# schematic.net
KiCad netlist of a schematic drawn in EAGLE
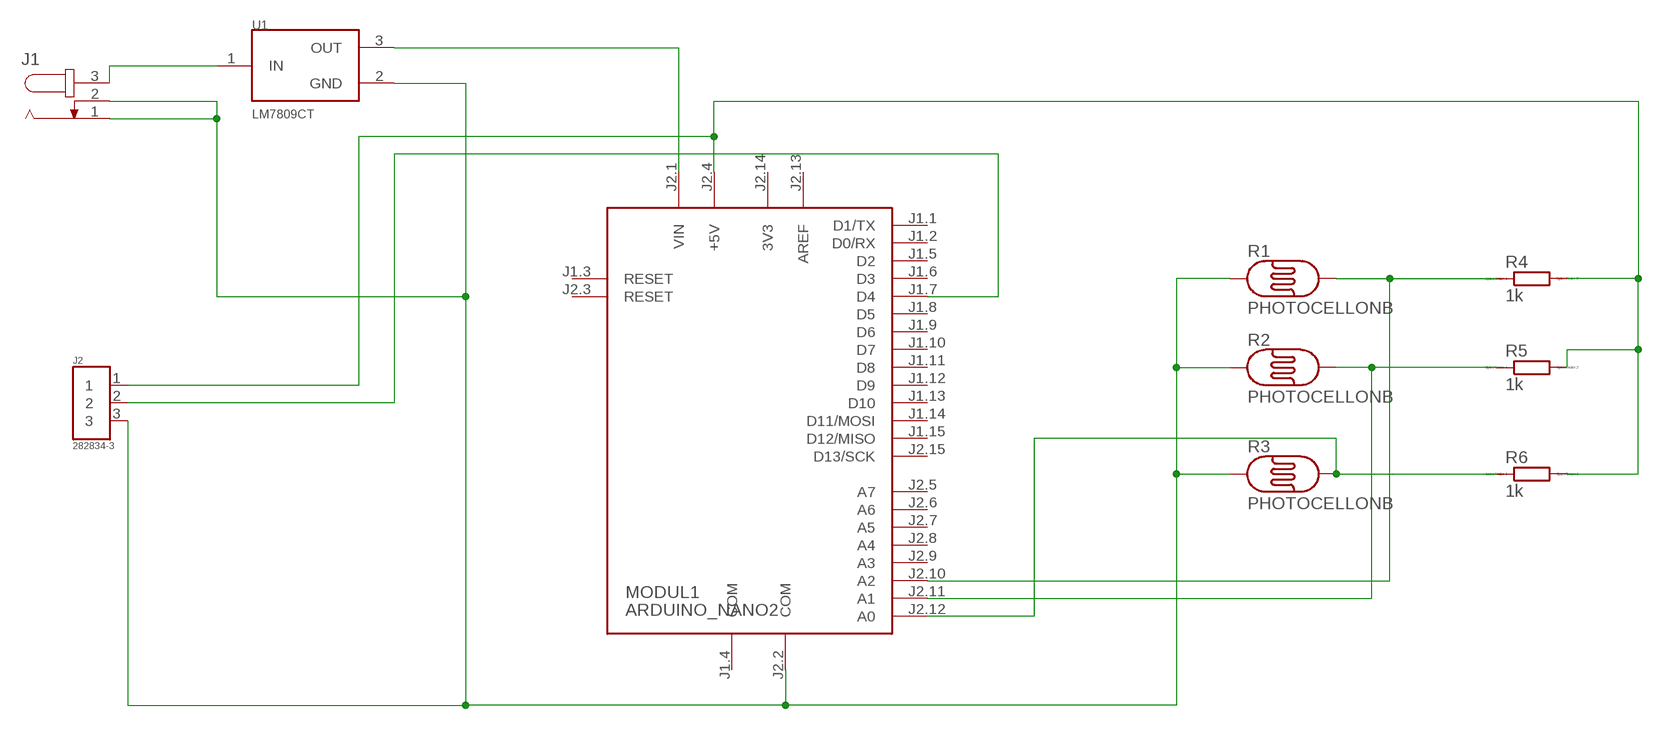
[diagram p0: schematic, sheet 1]

(export (version "E")
  (design (tool "Eeschema 10.0.6"))
  (components
    (comp (ref "J1")
      (value "JACK-PLUG1")
      (footprint "eagle-import:SPC4078")
      (libsource (lib "eagle-import") (part "JACK-PLUG1"))
    )
    (comp (ref "J2")
      (value "282834-3")
      (footprint "eagle-import:TE_282834-3")
      (fields (field (name "MF") "TE Connectivity"))
      (libsource (lib "eagle-import") (part "282834-3"))
    )
    (comp (ref "MODUL1")
      (value "ARDUINO_NANO2")
      (footprint "eagle-import:ARDUINO_NANO2")
      (libsource (lib "eagle-import") (part "ARDUINO_NANO2"))
    )
    (comp (ref "R1")
      (value "PHOTOCELLONB")
      (footprint "eagle-import:ON_BOARD")
      (libsource (lib "eagle-import") (part "PHOTOCELLONB"))
    )
    (comp (ref "R2")
      (value "PHOTOCELLONB")
      (footprint "eagle-import:ON_BOARD")
      (libsource (lib "eagle-import") (part "PHOTOCELLONB"))
    )
    (comp (ref "R3")
      (value "PHOTOCELLONB")
      (footprint "eagle-import:ON_BOARD")
      (libsource (lib "eagle-import") (part "PHOTOCELLONB"))
    )
    (comp (ref "R4")
      (value "1k")
      (footprint "eagle-import:0207_10")
      (libsource (lib "eagle-import") (part "R0207/10"))
    )
    (comp (ref "R5")
      (value "1k")
      (footprint "eagle-import:0207_10")
      (libsource (lib "eagle-import") (part "R0207/10"))
    )
    (comp (ref "R6")
      (value "1k")
      (footprint "eagle-import:0207_10")
      (libsource (lib "eagle-import") (part "R0207/10"))
    )
    (comp (ref "U1")
      (value "LM7809CT")
      (footprint "eagle-import:TO254P470X1016X1879-3P")
      (fields (field (name "MF") "ON Semiconductor"))
      (libsource (lib "eagle-import") (part "LM7809CT"))
    )
  )
  (nets
    (net (code "1") (name "/3V3") (class "Default")
      (node (ref "MODUL1") (pin "J2.14") (pinfunction "3V3_J2.14") (pintype "power_in"))
    )
    (net (code "2") (name "/AREF") (class "Default")
      (node (ref "MODUL1") (pin "J2.13") (pinfunction "AREF_J2.13") (pintype "power_in"))
    )
    (net (code "3") (name "/COM") (class "Default")
      (node (ref "MODUL1") (pin "J1.4") (pinfunction "COM_J1.4") (pintype "power_in"))
    )
    (net (code "4") (name "Net-(MODUL1-+5V)") (class "Default")
      (node (ref "J2") (pin "1") (pinfunction "1_1") (pintype "passive"))
      (node (ref "MODUL1") (pin "J2.4") (pinfunction "+5V_J2.4") (pintype "power_in"))
      (node (ref "R4") (pin "2") (pinfunction "2_2") (pintype "passive"))
      (node (ref "R5") (pin "2") (pinfunction "2_2") (pintype "passive"))
      (node (ref "R6") (pin "2") (pinfunction "2_2") (pintype "passive"))
    )
    (net (code "5") (name "Net-(MODUL1-A0)") (class "Default")
      (node (ref "MODUL1") (pin "J2.12") (pinfunction "A0_J2.12") (pintype "bidirectional"))
      (node (ref "R3") (pin "2") (pinfunction "P$2_2") (pintype "bidirectional"))
      (node (ref "R6") (pin "1") (pinfunction "1_1") (pintype "passive"))
    )
    (net (code "6") (name "Net-(MODUL1-A1)") (class "Default")
      (node (ref "MODUL1") (pin "J2.11") (pinfunction "A1_J2.11") (pintype "bidirectional"))
      (node (ref "R2") (pin "2") (pinfunction "P$2_2") (pintype "bidirectional"))
      (node (ref "R5") (pin "1") (pinfunction "1_1") (pintype "passive"))
    )
    (net (code "7") (name "Net-(MODUL1-A2)") (class "Default")
      (node (ref "MODUL1") (pin "J2.10") (pinfunction "A2_J2.10") (pintype "bidirectional"))
      (node (ref "R1") (pin "2") (pinfunction "P$2_2") (pintype "bidirectional"))
      (node (ref "R4") (pin "1") (pinfunction "1_1") (pintype "passive"))
    )
    (net (code "8") (name "Net-(MODUL1-D4)") (class "Default")
      (node (ref "J2") (pin "2") (pinfunction "2_2") (pintype "passive"))
      (node (ref "MODUL1") (pin "J1.7") (pinfunction "D4_J1.7") (pintype "bidirectional"))
    )
    (net (code "9") (name "Net-(MODUL1-VIN)") (class "Default")
      (node (ref "MODUL1") (pin "J2.1") (pinfunction "VIN_J2.1") (pintype "power_in"))
      (node (ref "U1") (pin "3") (pinfunction "OUT_3") (pintype "output"))
    )
    (net (code "10") (name "Net-(R1-P$1)") (class "Default")
      (node (ref "J1") (pin "1") (pinfunction "1_1") (pintype "passive"))
      (node (ref "J1") (pin "2") (pinfunction "2_2") (pintype "passive"))
      (node (ref "J2") (pin "3") (pinfunction "3_3") (pintype "passive"))
      (node (ref "MODUL1") (pin "J2.2") (pinfunction "COM_J2.2") (pintype "power_in"))
      (node (ref "R1") (pin "1") (pinfunction "P$1_1") (pintype "bidirectional"))
      (node (ref "R2") (pin "1") (pinfunction "P$1_1") (pintype "bidirectional"))
      (node (ref "R3") (pin "1") (pinfunction "P$1_1") (pintype "bidirectional"))
      (node (ref "U1") (pin "2") (pinfunction "GND_2") (pintype "power_in"))
    )
    (net (code "11") (name "Net-(U1-IN)") (class "Default")
      (node (ref "J1") (pin "3") (pinfunction "3_3") (pintype "passive"))
      (node (ref "U1") (pin "1") (pinfunction "IN_1") (pintype "input"))
    )
    (net (code "12") (name "unconnected-(MODUL1-A3-PadJ2.9)") (class "Default")
      (node (ref "MODUL1") (pin "J2.9") (pinfunction "A3_J2.9") (pintype "bidirectional"))
    )
    (net (code "13") (name "unconnected-(MODUL1-A4-PadJ2.8)") (class "Default")
      (node (ref "MODUL1") (pin "J2.8") (pinfunction "A4_J2.8") (pintype "bidirectional"))
    )
    (net (code "14") (name "unconnected-(MODUL1-A5-PadJ2.7)") (class "Default")
      (node (ref "MODUL1") (pin "J2.7") (pinfunction "A5_J2.7") (pintype "bidirectional"))
    )
    (net (code "15") (name "unconnected-(MODUL1-A6-PadJ2.6)") (class "Default")
      (node (ref "MODUL1") (pin "J2.6") (pinfunction "A6_J2.6") (pintype "bidirectional"))
    )
    (net (code "16") (name "unconnected-(MODUL1-A7-PadJ2.5)") (class "Default")
      (node (ref "MODUL1") (pin "J2.5") (pinfunction "A7_J2.5") (pintype "bidirectional"))
    )
    (net (code "17") (name "unconnected-(MODUL1-D0{slash}RX-PadJ1.2)") (class "Default")
      (node (ref "MODUL1") (pin "J1.2") (pinfunction "D0/RX_J1.2") (pintype "bidirectional"))
    )
    (net (code "18") (name "unconnected-(MODUL1-D1{slash}TX-PadJ1.1)") (class "Default")
      (node (ref "MODUL1") (pin "J1.1") (pinfunction "D1/TX_J1.1") (pintype "bidirectional"))
    )
    (net (code "19") (name "unconnected-(MODUL1-D2-PadJ1.5)") (class "Default")
      (node (ref "MODUL1") (pin "J1.5") (pinfunction "D2_J1.5") (pintype "bidirectional"))
    )
    (net (code "20") (name "unconnected-(MODUL1-D3-PadJ1.6)") (class "Default")
      (node (ref "MODUL1") (pin "J1.6") (pinfunction "D3_J1.6") (pintype "bidirectional"))
    )
    (net (code "21") (name "unconnected-(MODUL1-D5-PadJ1.8)") (class "Default")
      (node (ref "MODUL1") (pin "J1.8") (pinfunction "D5_J1.8") (pintype "bidirectional"))
    )
    (net (code "22") (name "unconnected-(MODUL1-D6-PadJ1.9)") (class "Default")
      (node (ref "MODUL1") (pin "J1.9") (pinfunction "D6_J1.9") (pintype "bidirectional"))
    )
    (net (code "23") (name "unconnected-(MODUL1-D7-PadJ1.10)") (class "Default")
      (node (ref "MODUL1") (pin "J1.10") (pinfunction "D7_J1.10") (pintype "bidirectional"))
    )
    (net (code "24") (name "unconnected-(MODUL1-D8-PadJ1.11)") (class "Default")
      (node (ref "MODUL1") (pin "J1.11") (pinfunction "D8_J1.11") (pintype "bidirectional"))
    )
    (net (code "25") (name "unconnected-(MODUL1-D9-PadJ1.12)") (class "Default")
      (node (ref "MODUL1") (pin "J1.12") (pinfunction "D9_J1.12") (pintype "bidirectional"))
    )
    (net (code "26") (name "unconnected-(MODUL1-D10-PadJ1.13)") (class "Default")
      (node (ref "MODUL1") (pin "J1.13") (pinfunction "D10_J1.13") (pintype "bidirectional"))
    )
    (net (code "27") (name "unconnected-(MODUL1-D11{slash}MOSI-PadJ1.14)") (class "Default")
      (node (ref "MODUL1") (pin "J1.14") (pinfunction "D11/MOSI_J1.14") (pintype "bidirectional"))
    )
    (net (code "28") (name "unconnected-(MODUL1-D12{slash}MISO-PadJ1.15)") (class "Default")
      (node (ref "MODUL1") (pin "J1.15") (pinfunction "D12/MISO_J1.15") (pintype "bidirectional"))
    )
    (net (code "29") (name "unconnected-(MODUL1-D13{slash}SCK-PadJ2.15)") (class "Default")
      (node (ref "MODUL1") (pin "J2.15") (pinfunction "D13/SCK_J2.15") (pintype "bidirectional"))
    )
    (net (code "30") (name "unconnected-(MODUL1-RESET-PadJ1.3)") (class "Default")
      (node (ref "MODUL1") (pin "J1.3") (pinfunction "RESET_J1.3") (pintype "bidirectional"))
    )
    (net (code "31") (name "unconnected-(MODUL1-RESET-PadJ2.3)") (class "Default")
      (node (ref "MODUL1") (pin "J2.3") (pinfunction "RESET_J2.3") (pintype "bidirectional"))
    )
  )
)
